# motor_line.net
KiCad netlist of a schematic drawn in EAGLE
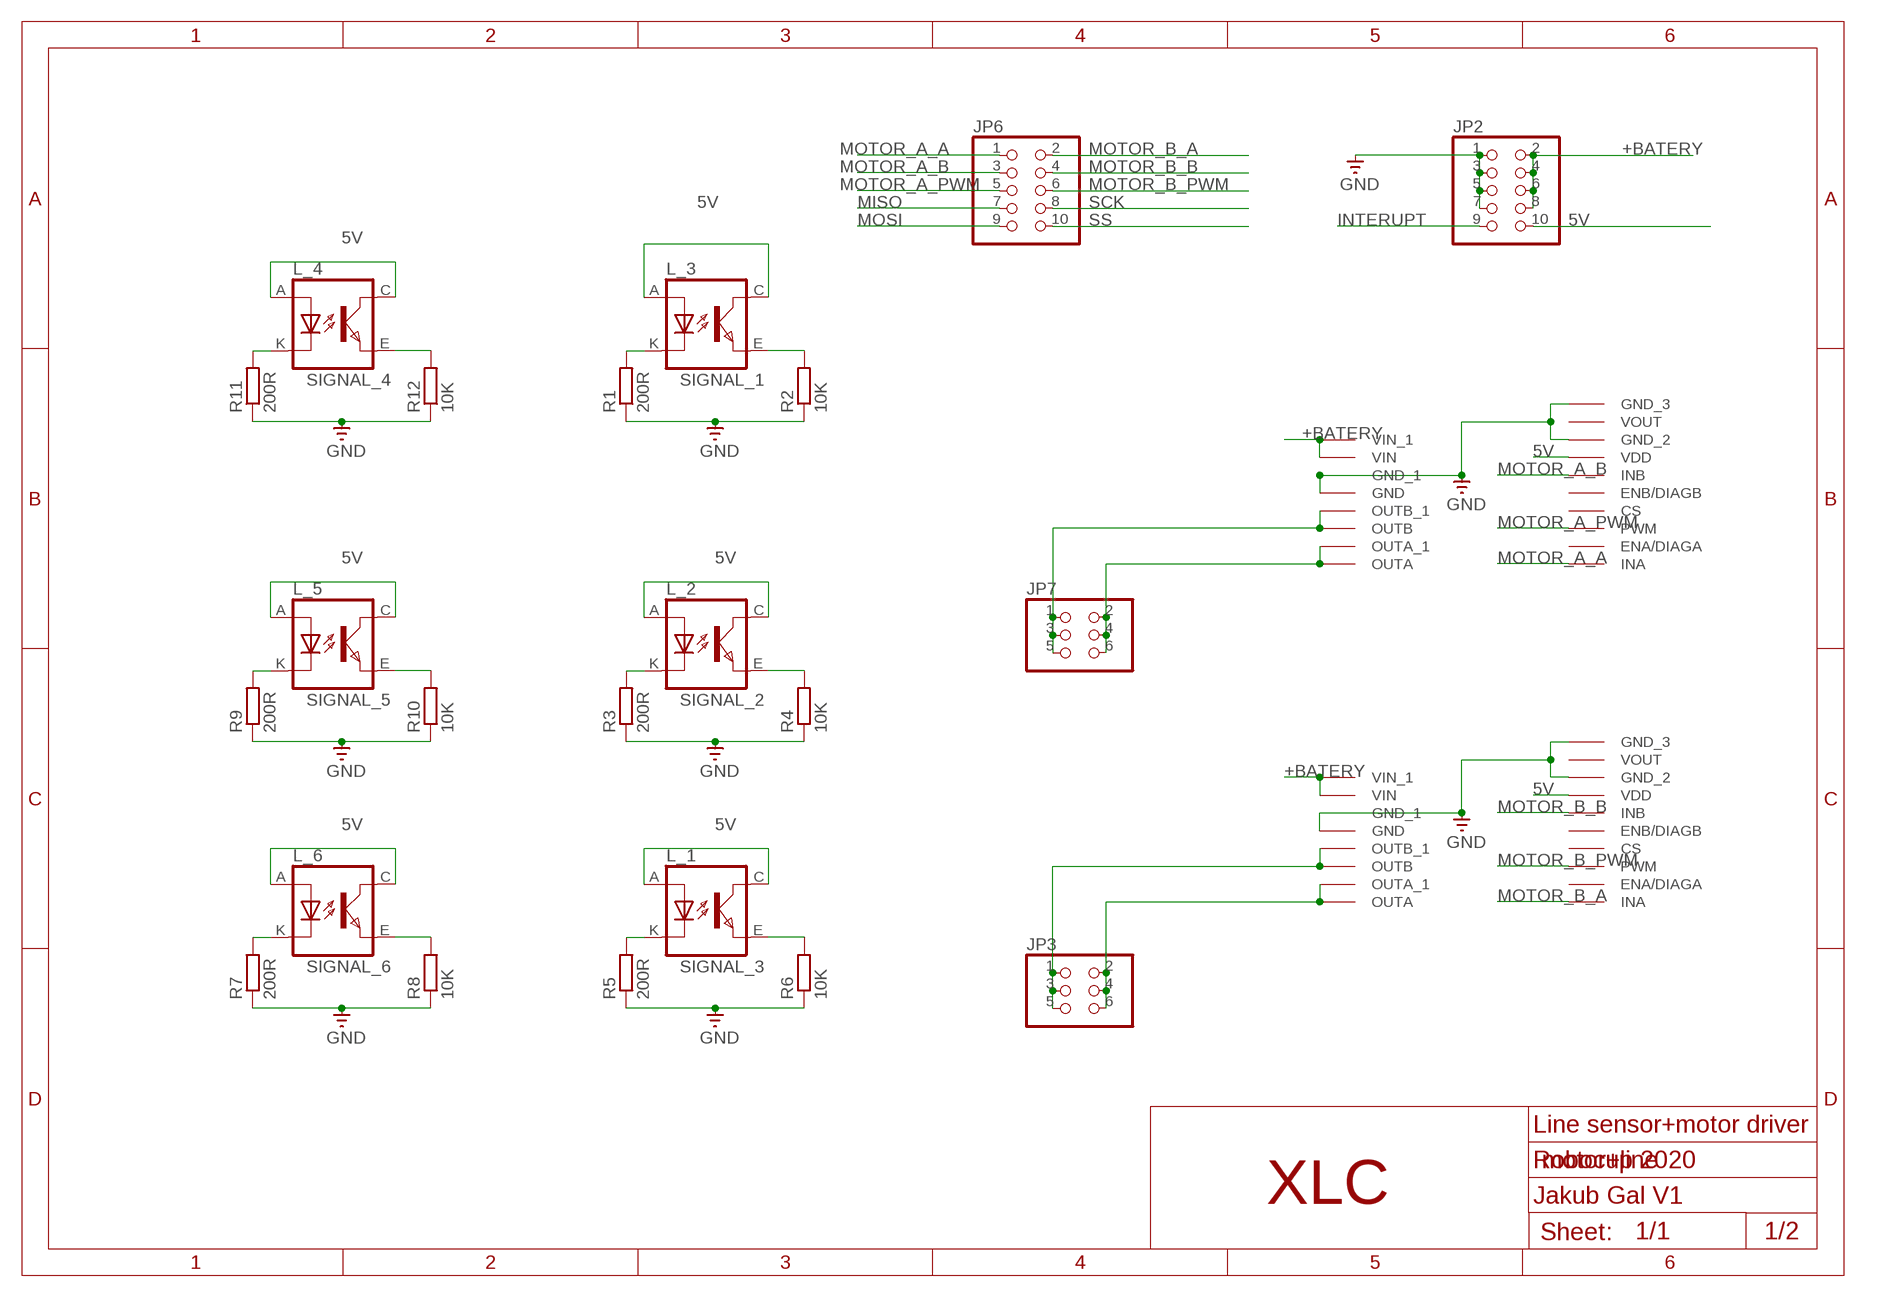
[diagram p0: schematic, sheet 1, part 1 of 2]
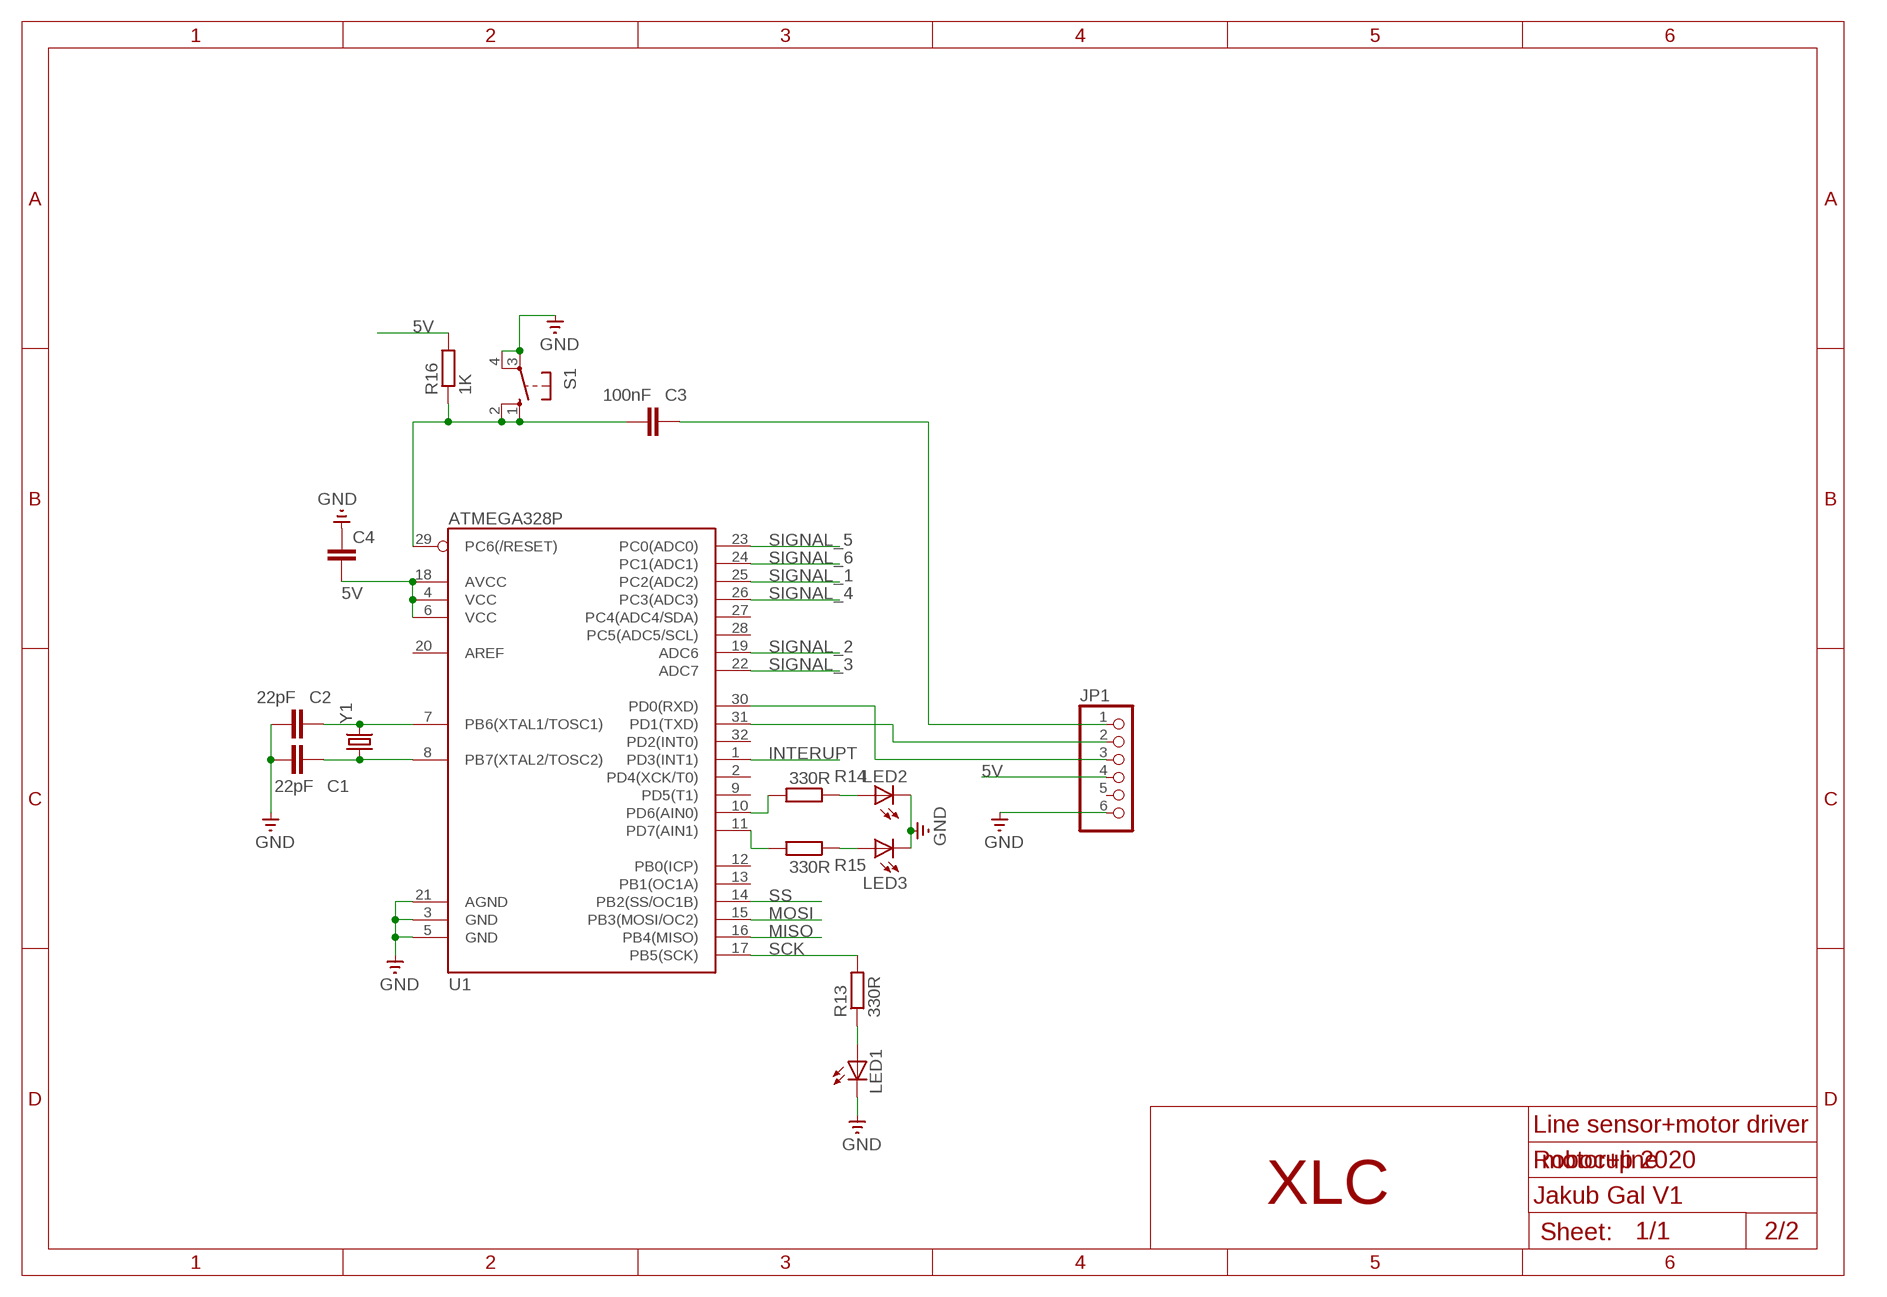
[diagram p1: schematic, sheet 1, part 2 of 2]

(export (version "E")
  (design (tool "Eeschema 10.0.6"))
  (components
    (comp (ref "C1")
      (value "22pF")
      (footprint "eagle-import:C0603")
      (libsource (lib "eagle-import") (part "C-EUC0603"))
    )
    (comp (ref "C2")
      (value "22pF")
      (footprint "eagle-import:C0603")
      (libsource (lib "eagle-import") (part "C-EUC0603"))
    )
    (comp (ref "C3")
      (value "100nF")
      (footprint "eagle-import:C0603")
      (libsource (lib "eagle-import") (part "C-EUC0603"))
    )
    (comp (ref "C4")
      (value "C-EUC0603")
      (footprint "eagle-import:C0603")
      (libsource (lib "eagle-import") (part "rcl_334_C-EUC0603"))
    )
    (comp (ref "JP1")
      (value "PINHD-1X6/90")
      (footprint "eagle-import:1X06_90")
      (libsource (lib "eagle-import") (part "PINHD-1X6/90"))
    )
    (comp (ref "JP2")
      (value "PINHD-2X5IDC")
      (footprint "eagle-import:2X05_IDC")
      (libsource (lib "eagle-import") (part "PINHD-2X5IDC"))
    )
    (comp (ref "JP3")
      (value "PINHD-2X3IDC")
      (footprint "eagle-import:2X03_IDC")
      (libsource (lib "eagle-import") (part "PINHD-2X3IDC"))
    )
    (comp (ref "JP6")
      (value "PINHD-2X5IDC")
      (footprint "eagle-import:2X05_IDC")
      (libsource (lib "eagle-import") (part "PINHD-2X5IDC"))
    )
    (comp (ref "JP7")
      (value "PINHD-2X3IDC")
      (footprint "eagle-import:2X03_IDC")
      (libsource (lib "eagle-import") (part "PINHD-2X3IDC"))
    )
    (comp (ref "LED1")
      (value "LEDCHIPLED_0603")
      (footprint "eagle-import:CHIPLED_0603")
      (libsource (lib "eagle-import") (part "LEDCHIPLED_0603"))
    )
    (comp (ref "LED2")
      (value "LEDCHIPLED_0603")
      (footprint "eagle-import:CHIPLED_0603")
      (libsource (lib "eagle-import") (part "LEDCHIPLED_0603"))
    )
    (comp (ref "LED3")
      (value "LEDCHIPLED_0603")
      (footprint "eagle-import:CHIPLED_0603")
      (libsource (lib "eagle-import") (part "LEDCHIPLED_0603"))
    )
    (comp (ref "L_1")
      (value "TCRT5000")
      (footprint "eagle-import:TCRT5000")
      (libsource (lib "eagle-import") (part "TCRT5000"))
    )
    (comp (ref "L_2")
      (value "TCRT5000")
      (footprint "eagle-import:TCRT5000")
      (libsource (lib "eagle-import") (part "TCRT5000"))
    )
    (comp (ref "L_3")
      (value "TCRT5000")
      (footprint "eagle-import:TCRT5000")
      (libsource (lib "eagle-import") (part "TCRT5000"))
    )
    (comp (ref "L_4")
      (value "TCRT5000")
      (footprint "eagle-import:TCRT5000")
      (fields (field (name "SPICEPREFIX") "O"))
      (libsource (lib "eagle-import") (part "TCRT5000"))
    )
    (comp (ref "L_5")
      (value "TCRT5000")
      (footprint "eagle-import:TCRT5000")
      (libsource (lib "eagle-import") (part "TCRT5000"))
    )
    (comp (ref "L_6")
      (value "TCRT5000")
      (footprint "eagle-import:TCRT5000")
      (fields (field (name "SPICEPREFIX") "O"))
      (libsource (lib "eagle-import") (part "TCRT5000"))
    )
    (comp (ref "R1")
      (value "200R")
      (footprint "eagle-import:R0603")
      (libsource (lib "eagle-import") (part "R-EU_R0603"))
    )
    (comp (ref "R2")
      (value "10K")
      (footprint "eagle-import:R0603")
      (libsource (lib "eagle-import") (part "R-EU_R0603"))
    )
    (comp (ref "R3")
      (value "200R")
      (footprint "eagle-import:R0603")
      (libsource (lib "eagle-import") (part "R-EU_R0603"))
    )
    (comp (ref "R4")
      (value "10K")
      (footprint "eagle-import:R0603")
      (libsource (lib "eagle-import") (part "R-EU_R0603"))
    )
    (comp (ref "R5")
      (value "200R")
      (footprint "eagle-import:R0603")
      (libsource (lib "eagle-import") (part "R-EU_R0603"))
    )
    (comp (ref "R6")
      (value "10K")
      (footprint "eagle-import:R0603")
      (libsource (lib "eagle-import") (part "R-EU_R0603"))
    )
    (comp (ref "R7")
      (value "200R")
      (footprint "eagle-import:R0603")
      (libsource (lib "eagle-import") (part "R-EU_R0603"))
    )
    (comp (ref "R8")
      (value "10K")
      (footprint "eagle-import:R0603")
      (libsource (lib "eagle-import") (part "R-EU_R0603"))
    )
    (comp (ref "R9")
      (value "200R")
      (footprint "eagle-import:R0603")
      (libsource (lib "eagle-import") (part "R-EU_R0603"))
    )
    (comp (ref "R10")
      (value "10K")
      (footprint "eagle-import:R0603")
      (libsource (lib "eagle-import") (part "R-EU_R0603"))
    )
    (comp (ref "R11")
      (value "200R")
      (footprint "eagle-import:R0603")
      (libsource (lib "eagle-import") (part "R-EU_R0603"))
    )
    (comp (ref "R12")
      (value "10K")
      (footprint "eagle-import:R0603")
      (libsource (lib "eagle-import") (part "R-EU_R0603"))
    )
    (comp (ref "R13")
      (value "330R")
      (footprint "eagle-import:R0603")
      (libsource (lib "eagle-import") (part "R-EU_R0603"))
    )
    (comp (ref "R14")
      (value "330R")
      (footprint "eagle-import:R0603")
      (libsource (lib "eagle-import") (part "R-EU_R0603"))
    )
    (comp (ref "R15")
      (value "330R")
      (footprint "eagle-import:R0603")
      (libsource (lib "eagle-import") (part "R-EU_R0603"))
    )
    (comp (ref "R16")
      (value "1K")
      (footprint "eagle-import:R0603")
      (libsource (lib "eagle-import") (part "R-EU_R0603"))
    )
    (comp (ref "S1")
      (value "10-XX")
      (footprint "eagle-import:B3F-10XX")
      (fields (field (name "MPN") "B3F-1000"))
      (libsource (lib "eagle-import") (part "10-XX"))
    )
    (comp (ref "U$1")
      (value "MOTOR_DRIVER")
      (footprint "eagle-import:MOTOR_DRIVER")
      (libsource (lib "eagle-import") (part "MOTOR_DRIVER"))
    )
    (comp (ref "U$2")
      (value "MOTOR_DRIVER")
      (footprint "eagle-import:MOTOR_DRIVER")
      (libsource (lib "eagle-import") (part "MOTOR_DRIVER"))
    )
    (comp (ref "U1")
      (value "ATMEGA328P")
      (footprint "eagle-import:TQFP32-08")
      (libsource (lib "eagle-import") (part "ATMEGA328_SMT"))
    )
    (comp (ref "Y1")
      (value "CRYSTALHC49US")
      (footprint "eagle-import:HC49US")
      (libsource (lib "eagle-import") (part "CRYSTALHC49US"))
    )
  )
  (nets
    (net (code "1") (name "/+BATERY") (class "Default")
      (node (ref "JP2") (pin "2") (pinfunction "2_2") (pintype "passive"))
      (node (ref "JP2") (pin "4") (pinfunction "4_4") (pintype "passive"))
      (node (ref "JP2") (pin "6") (pinfunction "6_6") (pintype "passive"))
      (node (ref "JP2") (pin "8") (pinfunction "8_8") (pintype "passive"))
      (node (ref "U$1") (pin "VIN") (pinfunction "VIN_VIN") (pintype "bidirectional"))
      (node (ref "U$1") (pin "VIN_1") (pinfunction "VIN_1_VIN_1") (pintype "bidirectional"))
      (node (ref "U$2") (pin "VIN") (pinfunction "VIN_VIN") (pintype "bidirectional"))
      (node (ref "U$2") (pin "VIN_1") (pinfunction "VIN_1_VIN_1") (pintype "bidirectional"))
    )
    (net (code "2") (name "/5V") (class "Default")
      (node (ref "C4") (pin "2") (pinfunction "2_2") (pintype "passive"))
      (node (ref "JP1") (pin "4") (pinfunction "4_4") (pintype "passive"))
      (node (ref "JP2") (pin "10") (pinfunction "10_10") (pintype "passive"))
      (node (ref "L_1") (pin "A") (pinfunction "ANODE_A") (pintype "passive"))
      (node (ref "L_1") (pin "C") (pinfunction "COLLECTOR_C") (pintype "passive"))
      (node (ref "L_2") (pin "A") (pinfunction "ANODE_A") (pintype "passive"))
      (node (ref "L_2") (pin "C") (pinfunction "COLLECTOR_C") (pintype "passive"))
      (node (ref "L_3") (pin "A") (pinfunction "ANODE_A") (pintype "passive"))
      (node (ref "L_3") (pin "C") (pinfunction "COLLECTOR_C") (pintype "passive"))
      (node (ref "L_4") (pin "A") (pinfunction "ANODE_A") (pintype "passive"))
      (node (ref "L_4") (pin "C") (pinfunction "COLLECTOR_C") (pintype "passive"))
      (node (ref "L_5") (pin "A") (pinfunction "ANODE_A") (pintype "passive"))
      (node (ref "L_5") (pin "C") (pinfunction "COLLECTOR_C") (pintype "passive"))
      (node (ref "L_6") (pin "A") (pinfunction "ANODE_A") (pintype "passive"))
      (node (ref "L_6") (pin "C") (pinfunction "COLLECTOR_C") (pintype "passive"))
      (node (ref "R16") (pin "2") (pinfunction "2_2") (pintype "passive"))
      (node (ref "U$1") (pin "VDD") (pinfunction "VDD_VDD") (pintype "bidirectional"))
      (node (ref "U$2") (pin "VDD") (pinfunction "VDD_VDD") (pintype "bidirectional"))
      (node (ref "U1") (pin "18") (pinfunction "AVCC_18") (pintype "bidirectional"))
      (node (ref "U1") (pin "4") (pinfunction "VCC_4") (pintype "bidirectional"))
      (node (ref "U1") (pin "6") (pinfunction "VCC_6") (pintype "bidirectional"))
    )
    (net (code "3") (name "/INTERUPT") (class "Default")
      (node (ref "JP2") (pin "9") (pinfunction "9_9") (pintype "passive"))
      (node (ref "U1") (pin "1") (pinfunction "PD3(INT1)_1") (pintype "bidirectional"))
    )
    (net (code "4") (name "/MISO") (class "Default")
      (node (ref "JP6") (pin "7") (pinfunction "7_7") (pintype "passive"))
      (node (ref "U1") (pin "16") (pinfunction "PB4(MISO)_16") (pintype "bidirectional"))
    )
    (net (code "5") (name "/MOSI") (class "Default")
      (node (ref "JP6") (pin "9") (pinfunction "9_9") (pintype "passive"))
      (node (ref "U1") (pin "15") (pinfunction "PB3(MOSI/OC2)_15") (pintype "bidirectional"))
    )
    (net (code "6") (name "/MOTOR_A_A") (class "Default")
      (node (ref "JP6") (pin "1") (pinfunction "1_1") (pintype "passive"))
      (node (ref "U$1") (pin "INA") (pinfunction "INA_INA") (pintype "bidirectional"))
    )
    (net (code "7") (name "/MOTOR_A_B") (class "Default")
      (node (ref "JP6") (pin "3") (pinfunction "3_3") (pintype "passive"))
      (node (ref "U$1") (pin "INB") (pinfunction "INB_INB") (pintype "bidirectional"))
    )
    (net (code "8") (name "/MOTOR_A_PWM") (class "Default")
      (node (ref "JP6") (pin "5") (pinfunction "5_5") (pintype "passive"))
      (node (ref "U$1") (pin "PWM") (pinfunction "PWM_PWM") (pintype "bidirectional"))
    )
    (net (code "9") (name "/MOTOR_B_A") (class "Default")
      (node (ref "JP6") (pin "2") (pinfunction "2_2") (pintype "passive"))
      (node (ref "U$2") (pin "INA") (pinfunction "INA_INA") (pintype "bidirectional"))
    )
    (net (code "10") (name "/MOTOR_B_B") (class "Default")
      (node (ref "JP6") (pin "4") (pinfunction "4_4") (pintype "passive"))
      (node (ref "U$2") (pin "INB") (pinfunction "INB_INB") (pintype "bidirectional"))
    )
    (net (code "11") (name "/MOTOR_B_PWM") (class "Default")
      (node (ref "JP6") (pin "6") (pinfunction "6_6") (pintype "passive"))
      (node (ref "U$2") (pin "PWM") (pinfunction "PWM_PWM") (pintype "bidirectional"))
    )
    (net (code "12") (name "/SCK") (class "Default")
      (node (ref "JP6") (pin "8") (pinfunction "8_8") (pintype "passive"))
      (node (ref "R13") (pin "2") (pinfunction "2_2") (pintype "passive"))
      (node (ref "U1") (pin "17") (pinfunction "PB5(SCK)_17") (pintype "bidirectional"))
    )
    (net (code "13") (name "/SIGNAL_1") (class "Default")
      (node (ref "L_3") (pin "E") (pinfunction "EMITTER_E") (pintype "passive"))
      (node (ref "R2") (pin "2") (pinfunction "2_2") (pintype "passive"))
      (node (ref "U1") (pin "25") (pinfunction "PC2(ADC2)_25") (pintype "bidirectional"))
    )
    (net (code "14") (name "/SIGNAL_2") (class "Default")
      (node (ref "L_2") (pin "E") (pinfunction "EMITTER_E") (pintype "passive"))
      (node (ref "R4") (pin "2") (pinfunction "2_2") (pintype "passive"))
      (node (ref "U1") (pin "19") (pinfunction "ADC6_19") (pintype "bidirectional"))
    )
    (net (code "15") (name "/SIGNAL_3") (class "Default")
      (node (ref "L_1") (pin "E") (pinfunction "EMITTER_E") (pintype "passive"))
      (node (ref "R6") (pin "2") (pinfunction "2_2") (pintype "passive"))
      (node (ref "U1") (pin "22") (pinfunction "ADC7_22") (pintype "bidirectional"))
    )
    (net (code "16") (name "/SIGNAL_4") (class "Default")
      (node (ref "L_4") (pin "E") (pinfunction "EMITTER_E") (pintype "passive"))
      (node (ref "R12") (pin "2") (pinfunction "2_2") (pintype "passive"))
      (node (ref "U1") (pin "26") (pinfunction "PC3(ADC3)_26") (pintype "bidirectional"))
    )
    (net (code "17") (name "/SIGNAL_5") (class "Default")
      (node (ref "L_5") (pin "E") (pinfunction "EMITTER_E") (pintype "passive"))
      (node (ref "R10") (pin "2") (pinfunction "2_2") (pintype "passive"))
      (node (ref "U1") (pin "23") (pinfunction "PC0(ADC0)_23") (pintype "bidirectional"))
    )
    (net (code "18") (name "/SIGNAL_6") (class "Default")
      (node (ref "L_6") (pin "E") (pinfunction "EMITTER_E") (pintype "passive"))
      (node (ref "R8") (pin "2") (pinfunction "2_2") (pintype "passive"))
      (node (ref "U1") (pin "24") (pinfunction "PC1(ADC1)_24") (pintype "bidirectional"))
    )
    (net (code "19") (name "/SS") (class "Default")
      (node (ref "JP6") (pin "10") (pinfunction "10_10") (pintype "passive"))
      (node (ref "U1") (pin "14") (pinfunction "PB2(SS/OC1B)_14") (pintype "bidirectional"))
    )
    (net (code "20") (name "GND") (class "Default")
      (node (ref "C1") (pin "1") (pinfunction "1_1") (pintype "passive"))
      (node (ref "C2") (pin "1") (pinfunction "1_1") (pintype "passive"))
      (node (ref "C4") (pin "1") (pinfunction "1_1") (pintype "passive"))
      (node (ref "JP1") (pin "6") (pinfunction "6_6") (pintype "passive"))
      (node (ref "JP2") (pin "1") (pinfunction "1_1") (pintype "passive"))
      (node (ref "JP2") (pin "3") (pinfunction "3_3") (pintype "passive"))
      (node (ref "JP2") (pin "5") (pinfunction "5_5") (pintype "passive"))
      (node (ref "JP2") (pin "7") (pinfunction "7_7") (pintype "passive"))
      (node (ref "LED1") (pin "C") (pinfunction "C_C") (pintype "passive"))
      (node (ref "LED2") (pin "C") (pinfunction "C_C") (pintype "passive"))
      (node (ref "LED3") (pin "C") (pinfunction "C_C") (pintype "passive"))
      (node (ref "R1") (pin "1") (pinfunction "1_1") (pintype "passive"))
      (node (ref "R10") (pin "1") (pinfunction "1_1") (pintype "passive"))
      (node (ref "R11") (pin "1") (pinfunction "1_1") (pintype "passive"))
      (node (ref "R12") (pin "1") (pinfunction "1_1") (pintype "passive"))
      (node (ref "R2") (pin "1") (pinfunction "1_1") (pintype "passive"))
      (node (ref "R3") (pin "1") (pinfunction "1_1") (pintype "passive"))
      (node (ref "R4") (pin "1") (pinfunction "1_1") (pintype "passive"))
      (node (ref "R5") (pin "1") (pinfunction "1_1") (pintype "passive"))
      (node (ref "R6") (pin "1") (pinfunction "1_1") (pintype "passive"))
      (node (ref "R7") (pin "1") (pinfunction "1_1") (pintype "passive"))
      (node (ref "R8") (pin "1") (pinfunction "1_1") (pintype "passive"))
      (node (ref "R9") (pin "1") (pinfunction "1_1") (pintype "passive"))
      (node (ref "S1") (pin "3") (pinfunction "P_3") (pintype "passive"))
      (node (ref "S1") (pin "4") (pinfunction "P1_4") (pintype "passive"))
      (node (ref "U$1") (pin "GND") (pinfunction "GND_GND") (pintype "bidirectional"))
      (node (ref "U$1") (pin "GND_1") (pinfunction "GND_1_GND_1") (pintype "bidirectional"))
      (node (ref "U$1") (pin "GND_2") (pinfunction "GND_2_GND_2") (pintype "bidirectional"))
      (node (ref "U$1") (pin "GND_3") (pinfunction "GND_3_GND_3") (pintype "bidirectional"))
      (node (ref "U$2") (pin "GND") (pinfunction "GND_GND") (pintype "bidirectional"))
      (node (ref "U$2") (pin "GND_1") (pinfunction "GND_1_GND_1") (pintype "bidirectional"))
      (node (ref "U$2") (pin "GND_2") (pinfunction "GND_2_GND_2") (pintype "bidirectional"))
      (node (ref "U$2") (pin "GND_3") (pinfunction "GND_3_GND_3") (pintype "bidirectional"))
      (node (ref "U1") (pin "21") (pinfunction "AGND_21") (pintype "bidirectional"))
      (node (ref "U1") (pin "3") (pinfunction "GND_3") (pintype "bidirectional"))
      (node (ref "U1") (pin "5") (pinfunction "GND_5") (pintype "bidirectional"))
    )
    (net (code "21") (name "Net-(C3-Pad2)") (class "Default")
      (node (ref "C3") (pin "2") (pinfunction "2_2") (pintype "passive"))
      (node (ref "JP1") (pin "1") (pinfunction "1_1") (pintype "passive"))
    )
    (net (code "22") (name "Net-(JP3-Pad1)") (class "Default")
      (node (ref "JP3") (pin "1") (pinfunction "1_1") (pintype "passive"))
      (node (ref "JP3") (pin "3") (pinfunction "3_3") (pintype "passive"))
      (node (ref "JP3") (pin "5") (pinfunction "5_5") (pintype "passive"))
      (node (ref "U$2") (pin "OUTB") (pinfunction "OUTB_OUTB") (pintype "bidirectional"))
      (node (ref "U$2") (pin "OUTB_1") (pinfunction "OUTB_1_OUTB_1") (pintype "bidirectional"))
    )
    (net (code "23") (name "Net-(JP3-Pad2)") (class "Default")
      (node (ref "JP3") (pin "2") (pinfunction "2_2") (pintype "passive"))
      (node (ref "JP3") (pin "4") (pinfunction "4_4") (pintype "passive"))
      (node (ref "JP3") (pin "6") (pinfunction "6_6") (pintype "passive"))
      (node (ref "U$2") (pin "OUTA") (pinfunction "OUTA_OUTA") (pintype "bidirectional"))
      (node (ref "U$2") (pin "OUTA_1") (pinfunction "OUTA_1_OUTA_1") (pintype "bidirectional"))
    )
    (net (code "24") (name "Net-(JP7-Pad1)") (class "Default")
      (node (ref "JP7") (pin "1") (pinfunction "1_1") (pintype "passive"))
      (node (ref "JP7") (pin "3") (pinfunction "3_3") (pintype "passive"))
      (node (ref "JP7") (pin "5") (pinfunction "5_5") (pintype "passive"))
      (node (ref "U$1") (pin "OUTB") (pinfunction "OUTB_OUTB") (pintype "bidirectional"))
      (node (ref "U$1") (pin "OUTB_1") (pinfunction "OUTB_1_OUTB_1") (pintype "bidirectional"))
    )
    (net (code "25") (name "Net-(JP7-Pad2)") (class "Default")
      (node (ref "JP7") (pin "2") (pinfunction "2_2") (pintype "passive"))
      (node (ref "JP7") (pin "4") (pinfunction "4_4") (pintype "passive"))
      (node (ref "JP7") (pin "6") (pinfunction "6_6") (pintype "passive"))
      (node (ref "U$1") (pin "OUTA") (pinfunction "OUTA_OUTA") (pintype "bidirectional"))
      (node (ref "U$1") (pin "OUTA_1") (pinfunction "OUTA_1_OUTA_1") (pintype "bidirectional"))
    )
    (net (code "26") (name "Net-(LED1-PadA)") (class "Default")
      (node (ref "LED1") (pin "A") (pinfunction "A_A") (pintype "passive"))
      (node (ref "R13") (pin "1") (pinfunction "1_1") (pintype "passive"))
    )
    (net (code "27") (name "Net-(LED2-PadA)") (class "Default")
      (node (ref "LED2") (pin "A") (pinfunction "A_A") (pintype "passive"))
      (node (ref "R14") (pin "1") (pinfunction "1_1") (pintype "passive"))
    )
    (net (code "28") (name "Net-(LED3-PadA)") (class "Default")
      (node (ref "LED3") (pin "A") (pinfunction "A_A") (pintype "passive"))
      (node (ref "R15") (pin "1") (pinfunction "1_1") (pintype "passive"))
    )
    (net (code "29") (name "Net-(L_1-CATHODE)") (class "Default")
      (node (ref "L_1") (pin "K") (pinfunction "CATHODE_K") (pintype "passive"))
      (node (ref "R5") (pin "2") (pinfunction "2_2") (pintype "passive"))
    )
    (net (code "30") (name "Net-(L_2-CATHODE)") (class "Default")
      (node (ref "L_2") (pin "K") (pinfunction "CATHODE_K") (pintype "passive"))
      (node (ref "R3") (pin "2") (pinfunction "2_2") (pintype "passive"))
    )
    (net (code "31") (name "Net-(L_3-CATHODE)") (class "Default")
      (node (ref "L_3") (pin "K") (pinfunction "CATHODE_K") (pintype "passive"))
      (node (ref "R1") (pin "2") (pinfunction "2_2") (pintype "passive"))
    )
    (net (code "32") (name "Net-(L_4-CATHODE)") (class "Default")
      (node (ref "L_4") (pin "K") (pinfunction "CATHODE_K") (pintype "passive"))
      (node (ref "R11") (pin "2") (pinfunction "2_2") (pintype "passive"))
    )
    (net (code "33") (name "Net-(L_5-CATHODE)") (class "Default")
      (node (ref "L_5") (pin "K") (pinfunction "CATHODE_K") (pintype "passive"))
      (node (ref "R9") (pin "2") (pinfunction "2_2") (pintype "passive"))
    )
    (net (code "34") (name "Net-(L_6-CATHODE)") (class "Default")
      (node (ref "L_6") (pin "K") (pinfunction "CATHODE_K") (pintype "passive"))
      (node (ref "R7") (pin "2") (pinfunction "2_2") (pintype "passive"))
    )
    (net (code "35") (name "Net-(S1-S)") (class "Default")
      (node (ref "C3") (pin "1") (pinfunction "1_1") (pintype "passive"))
      (node (ref "R16") (pin "1") (pinfunction "1_1") (pintype "passive"))
      (node (ref "S1") (pin "1") (pinfunction "S_1") (pintype "passive"))
      (node (ref "S1") (pin "2") (pinfunction "S1_2") (pintype "passive"))
      (node (ref "U1") (pin "29") (pinfunction "PC6(/RESET)_29") (pintype "bidirectional"))
    )
    (net (code "36") (name "Net-(U1-PB6(XTAL1{slash}TOSC1))") (class "Default")
      (node (ref "C2") (pin "2") (pinfunction "2_2") (pintype "passive"))
      (node (ref "U1") (pin "7") (pinfunction "PB6(XTAL1/TOSC1)_7") (pintype "bidirectional"))
      (node (ref "Y1") (pin "2") (pinfunction "2_2") (pintype "passive"))
    )
    (net (code "37") (name "Net-(U1-PB7(XTAL2{slash}TOSC2))") (class "Default")
      (node (ref "C1") (pin "2") (pinfunction "2_2") (pintype "passive"))
      (node (ref "U1") (pin "8") (pinfunction "PB7(XTAL2/TOSC2)_8") (pintype "bidirectional"))
      (node (ref "Y1") (pin "1") (pinfunction "1_1") (pintype "passive"))
    )
    (net (code "38") (name "Net-(U1-PD0(RXD))") (class "Default")
      (node (ref "JP1") (pin "3") (pinfunction "3_3") (pintype "passive"))
      (node (ref "U1") (pin "30") (pinfunction "PD0(RXD)_30") (pintype "bidirectional"))
    )
    (net (code "39") (name "Net-(U1-PD1(TXD))") (class "Default")
      (node (ref "JP1") (pin "2") (pinfunction "2_2") (pintype "passive"))
      (node (ref "U1") (pin "31") (pinfunction "PD1(TXD)_31") (pintype "bidirectional"))
    )
    (net (code "40") (name "Net-(U1-PD6(AIN0))") (class "Default")
      (node (ref "R14") (pin "2") (pinfunction "2_2") (pintype "passive"))
      (node (ref "U1") (pin "10") (pinfunction "PD6(AIN0)_10") (pintype "bidirectional"))
    )
    (net (code "41") (name "Net-(U1-PD7(AIN1))") (class "Default")
      (node (ref "R15") (pin "2") (pinfunction "2_2") (pintype "passive"))
      (node (ref "U1") (pin "11") (pinfunction "PD7(AIN1)_11") (pintype "bidirectional"))
    )
    (net (code "42") (name "unconnected-(JP1-Pad5)") (class "Default")
      (node (ref "JP1") (pin "5") (pinfunction "5_5") (pintype "passive"))
    )
    (net (code "43") (name "unconnected-(U$1-PadCS)") (class "Default")
      (node (ref "U$1") (pin "CS") (pinfunction "CS_CS") (pintype "bidirectional"))
    )
    (net (code "44") (name "unconnected-(U$1-PadENA{slash}DIAGA)") (class "Default")
      (node (ref "U$1") (pin "ENA/DIAGA") (pinfunction "ENA/DIAGA_ENA/DIAGA") (pintype "bidirectional"))
    )
    (net (code "45") (name "unconnected-(U$1-PadENB{slash}DIAGB)") (class "Default")
      (node (ref "U$1") (pin "ENB/DIAGB") (pinfunction "ENB/DIAGB_ENB/DIAGB") (pintype "bidirectional"))
    )
    (net (code "46") (name "unconnected-(U$1-PadVOUT)") (class "Default")
      (node (ref "U$1") (pin "VOUT") (pinfunction "VOUT_VOUT") (pintype "bidirectional"))
    )
    (net (code "47") (name "unconnected-(U$2-PadCS)") (class "Default")
      (node (ref "U$2") (pin "CS") (pinfunction "CS_CS") (pintype "bidirectional"))
    )
    (net (code "48") (name "unconnected-(U$2-PadENA{slash}DIAGA)") (class "Default")
      (node (ref "U$2") (pin "ENA/DIAGA") (pinfunction "ENA/DIAGA_ENA/DIAGA") (pintype "bidirectional"))
    )
    (net (code "49") (name "unconnected-(U$2-PadENB{slash}DIAGB)") (class "Default")
      (node (ref "U$2") (pin "ENB/DIAGB") (pinfunction "ENB/DIAGB_ENB/DIAGB") (pintype "bidirectional"))
    )
    (net (code "50") (name "unconnected-(U$2-PadVOUT)") (class "Default")
      (node (ref "U$2") (pin "VOUT") (pinfunction "VOUT_VOUT") (pintype "bidirectional"))
    )
    (net (code "51") (name "unconnected-(U1-AREF-Pad20)") (class "Default")
      (node (ref "U1") (pin "20") (pinfunction "AREF_20") (pintype "bidirectional"))
    )
    (net (code "52") (name "unconnected-(U1-PB0(ICP)-Pad12)") (class "Default")
      (node (ref "U1") (pin "12") (pinfunction "PB0(ICP)_12") (pintype "bidirectional"))
    )
    (net (code "53") (name "unconnected-(U1-PB1(OC1A)-Pad13)") (class "Default")
      (node (ref "U1") (pin "13") (pinfunction "PB1(OC1A)_13") (pintype "bidirectional"))
    )
    (net (code "54") (name "unconnected-(U1-PC4(ADC4{slash}SDA)-Pad27)") (class "Default")
      (node (ref "U1") (pin "27") (pinfunction "PC4(ADC4/SDA)_27") (pintype "bidirectional"))
    )
    (net (code "55") (name "unconnected-(U1-PC5(ADC5{slash}SCL)-Pad28)") (class "Default")
      (node (ref "U1") (pin "28") (pinfunction "PC5(ADC5/SCL)_28") (pintype "bidirectional"))
    )
    (net (code "56") (name "unconnected-(U1-PD2(INT0)-Pad32)") (class "Default")
      (node (ref "U1") (pin "32") (pinfunction "PD2(INT0)_32") (pintype "bidirectional"))
    )
    (net (code "57") (name "unconnected-(U1-PD4(XCK{slash}T0)-Pad2)") (class "Default")
      (node (ref "U1") (pin "2") (pinfunction "PD4(XCK/T0)_2") (pintype "bidirectional"))
    )
    (net (code "58") (name "unconnected-(U1-PD5(T1)-Pad9)") (class "Default")
      (node (ref "U1") (pin "9") (pinfunction "PD5(T1)_9") (pintype "bidirectional"))
    )
  )
)
